# LB_BIT_iX_1IN_1OUT-MEDIUM-v03_1_1x.net
KiCad netlist of a schematic drawn in EAGLE
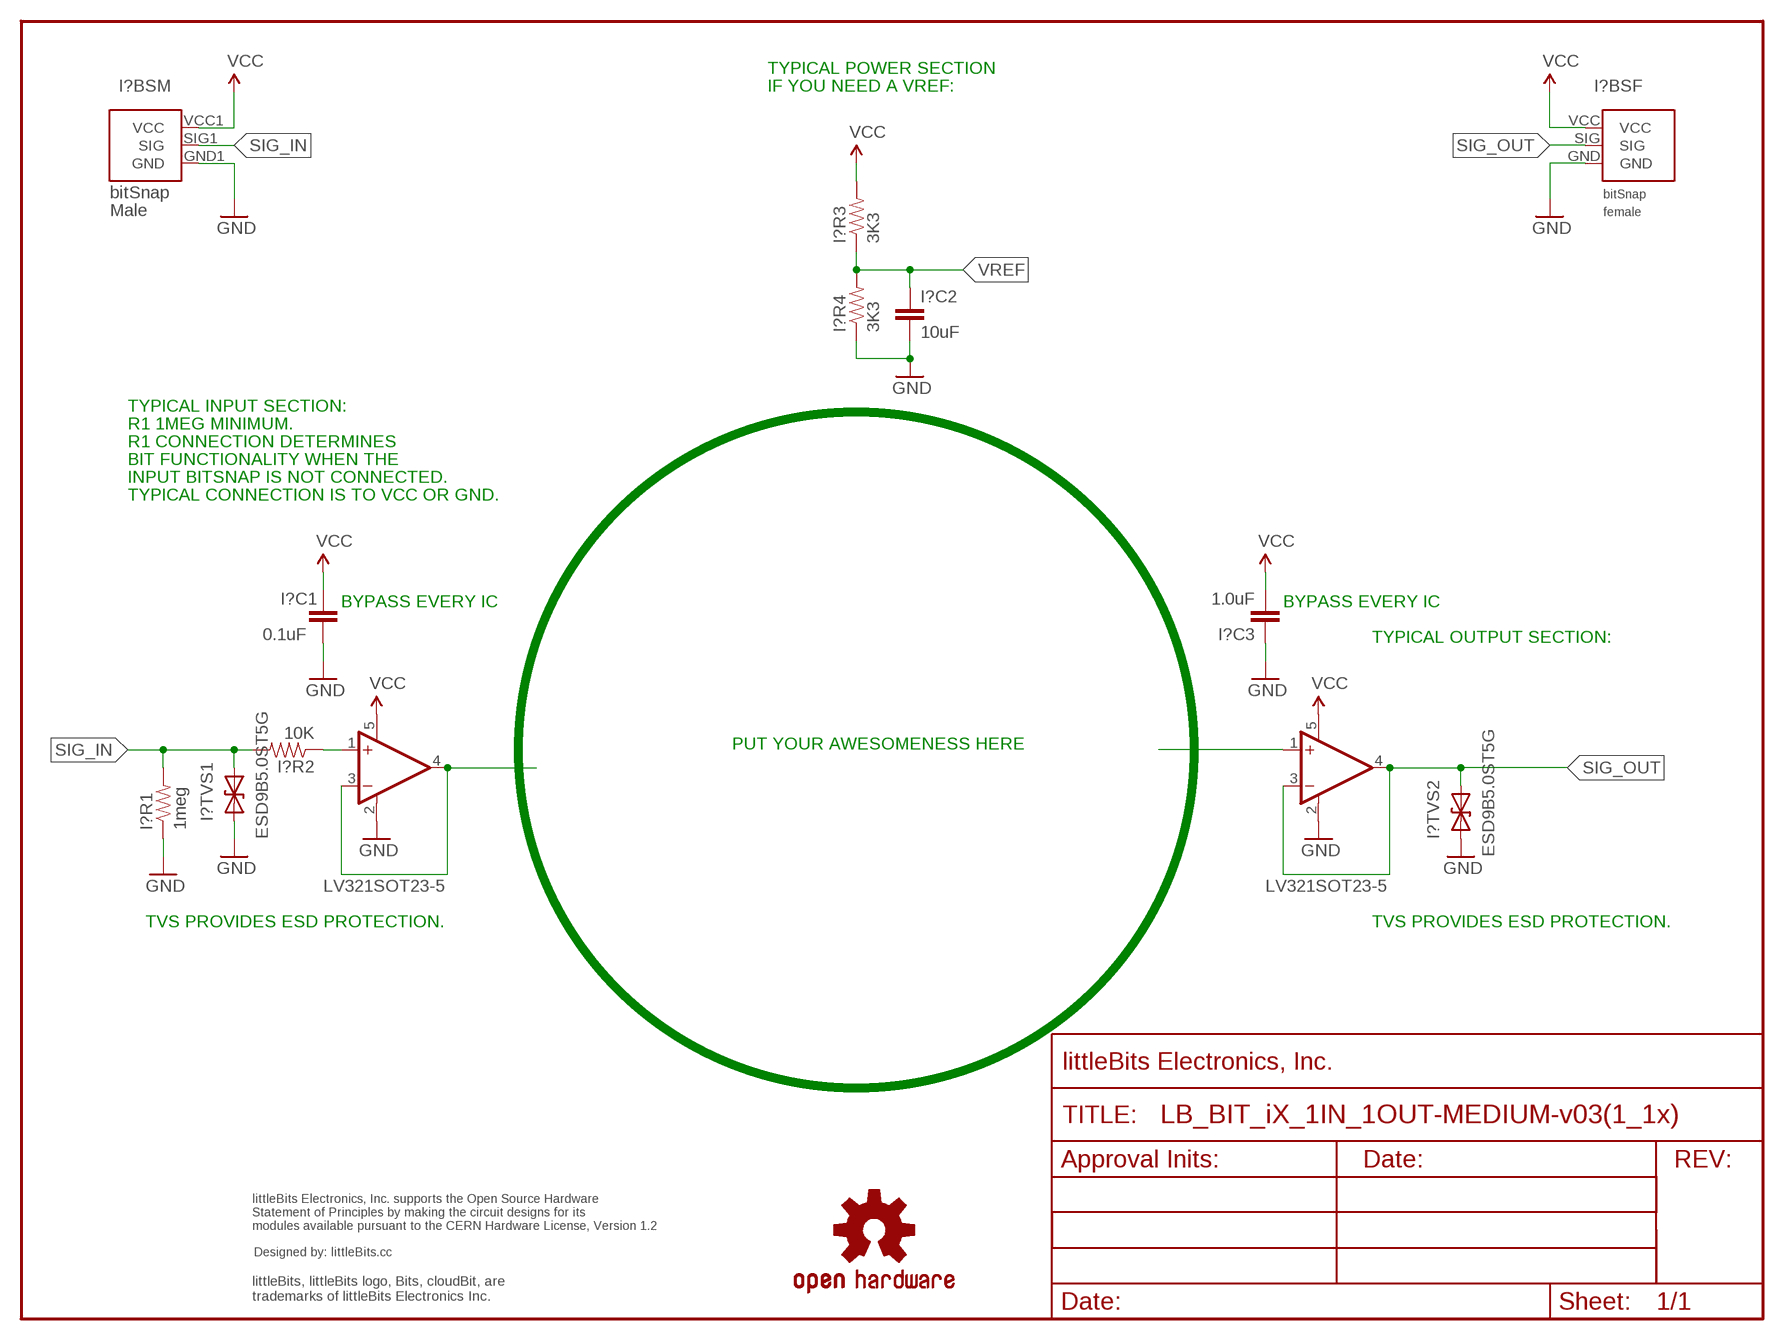
[diagram p0: schematic, sheet 1]

(export (version "E")
  (design (tool "Eeschema 10.0.6"))
  (components
    (comp (ref "I?BSF")
      (value "BITSNAP_V03_FEMALE")
      (footprint "eagle-import:BITSNAP_V03_FEMALE")
      (libsource (lib "eagle-import") (part "BITSNAP_V03_FEMALE"))
    )
    (comp (ref "I?BSM")
      (value "BITSNAP_V03_MALE")
      (footprint "eagle-import:BITSNAP_V03_MALE")
      (libsource (lib "eagle-import") (part "BITSNAP_V03_MALE"))
    )
    (comp (ref "I?C1")
      (value "0.1uF")
      (footprint "eagle-import:CAP-0603")
      (libsource (lib "eagle-import") (part "CAPCAP-0603"))
    )
    (comp (ref "I?C2")
      (value "10uF")
      (footprint "eagle-import:CAP-0603")
      (libsource (lib "eagle-import") (part "CAPCAP-0603"))
    )
    (comp (ref "I?C3")
      (value "1.0uF")
      (footprint "eagle-import:CAP-0603")
      (libsource (lib "eagle-import") (part "CAPCAP-0603"))
    )
    (comp (ref "I?R1")
      (value "1meg")
      (footprint "eagle-import:RES-0603")
      (libsource (lib "eagle-import") (part "RESISTOR0603"))
    )
    (comp (ref "I?R2")
      (value "10K")
      (footprint "eagle-import:RES-0603")
      (libsource (lib "eagle-import") (part "RESISTOR0603"))
    )
    (comp (ref "I?R3")
      (value "3K3")
      (footprint "eagle-import:RES-0603")
      (libsource (lib "eagle-import") (part "RESISTOR0603"))
    )
    (comp (ref "I?R4")
      (value "3K3")
      (footprint "eagle-import:RES-0603")
      (libsource (lib "eagle-import") (part "RESISTOR0603"))
    )
    (comp (ref "I?TVS1")
      (value "ESD9B5.0ST5G")
      (footprint "eagle-import:SOD-923")
      (libsource (lib "eagle-import") (part "DIODE-TVSSOD-923"))
    )
    (comp (ref "I?TVS2")
      (value "ESD9B5.0ST5G")
      (footprint "eagle-import:SOD-923")
      (libsource (lib "eagle-import") (part "DIODE-TVSSOD-923"))
    )
    (comp (ref "U$1")
      (value "FRAME-LETTER")
      (footprint "eagle-import:FABDWG01-OHW")
      (libsource (lib "eagle-import") (part "FRAME-LETTER"))
    )
    (comp (ref "U$2")
      (value "OSHWCREDIT")
      (footprint "eagle-import:OSHWCREDIT")
      (libsource (lib "eagle-import") (part "OSHWCREDIT"))
    )
    (comp (ref "U$3")
      (value "OSHW-LOGOL")
      (footprint "eagle-import:OSHW-LOGO-L")
      (libsource (lib "eagle-import") (part "OSHW-LOGOL"))
    )
    (comp (ref "U1")
      (value "LV321SOT23-5")
      (footprint "eagle-import:SOT23-5")
      (libsource (lib "eagle-import") (part "LV321SOT23-5"))
    )
    (comp (ref "U2")
      (value "LV321SOT23-5")
      (footprint "eagle-import:SOT23-5")
      (libsource (lib "eagle-import") (part "LV321SOT23-5"))
    )
  )
  (nets
    (net (code "1") (name "GND") (class "Default")
      (node (ref "I?BSF") (pin "GND") (pinfunction "GND_GND") (pintype "bidirectional"))
      (node (ref "I?BSM") (pin "GND1") (pinfunction "GND_GND1") (pintype "bidirectional"))
      (node (ref "I?C1") (pin "2") (pinfunction "2_2") (pintype "passive"))
      (node (ref "I?C2") (pin "2") (pinfunction "2_2") (pintype "passive"))
      (node (ref "I?C3") (pin "1") (pinfunction "1_1") (pintype "passive"))
      (node (ref "I?R1") (pin "1") (pinfunction "1_1") (pintype "passive"))
      (node (ref "I?R4") (pin "1") (pinfunction "1_1") (pintype "passive"))
      (node (ref "I?TVS1") (pin "1") (pinfunction "A_1") (pintype "passive"))
      (node (ref "I?TVS2") (pin "1") (pinfunction "A_1") (pintype "passive"))
      (node (ref "U1") (pin "2") (pinfunction "V-_2") (pintype "power_in"))
      (node (ref "U2") (pin "2") (pinfunction "V-_2") (pintype "power_in"))
    )
    (net (code "2") (name "Net-(U1-+IN)") (class "Default")
      (node (ref "I?R2") (pin "1") (pinfunction "1_1") (pintype "passive"))
      (node (ref "U1") (pin "1") (pinfunction "+IN_1") (pintype "input"))
    )
    (net (code "3") (name "Net-(U1--IN)") (class "Default")
      (node (ref "U1") (pin "3") (pinfunction "-IN_3") (pintype "input"))
      (node (ref "U1") (pin "4") (pinfunction "OUT_4") (pintype "output"))
    )
    (net (code "4") (name "SIG_IN") (class "Default")
      (node (ref "I?BSM") (pin "SIG1") (pinfunction "SIG_SIG1") (pintype "bidirectional"))
      (node (ref "I?R1") (pin "2") (pinfunction "2_2") (pintype "passive"))
      (node (ref "I?R2") (pin "2") (pinfunction "2_2") (pintype "passive"))
      (node (ref "I?TVS1") (pin "2") (pinfunction "C_2") (pintype "passive"))
    )
    (net (code "5") (name "SIG_OUT") (class "Default")
      (node (ref "I?BSF") (pin "SIG") (pinfunction "SIG_SIG") (pintype "bidirectional"))
      (node (ref "I?TVS2") (pin "2") (pinfunction "C_2") (pintype "passive"))
      (node (ref "U2") (pin "3") (pinfunction "-IN_3") (pintype "input"))
      (node (ref "U2") (pin "4") (pinfunction "OUT_4") (pintype "output"))
    )
    (net (code "6") (name "VCC") (class "Default")
      (node (ref "I?BSF") (pin "VCC") (pinfunction "VCC_VCC") (pintype "bidirectional"))
      (node (ref "I?BSM") (pin "VCC1") (pinfunction "VCC_VCC1") (pintype "bidirectional"))
      (node (ref "I?C1") (pin "1") (pinfunction "1_1") (pintype "passive"))
      (node (ref "I?C3") (pin "2") (pinfunction "2_2") (pintype "passive"))
      (node (ref "I?R3") (pin "2") (pinfunction "2_2") (pintype "passive"))
      (node (ref "U1") (pin "5") (pinfunction "V+_5") (pintype "power_in"))
      (node (ref "U2") (pin "5") (pinfunction "V+_5") (pintype "power_in"))
    )
    (net (code "7") (name "VREF") (class "Default")
      (node (ref "I?C2") (pin "1") (pinfunction "1_1") (pintype "passive"))
      (node (ref "I?R3") (pin "1") (pinfunction "1_1") (pintype "passive"))
      (node (ref "I?R4") (pin "2") (pinfunction "2_2") (pintype "passive"))
    )
    (net (code "8") (name "unconnected-(U2-+IN-Pad1)") (class "Default")
      (node (ref "U2") (pin "1") (pinfunction "+IN_1") (pintype "input"))
    )
  )
)
